# Enable_Circuit.net
KiCad netlist of a schematic drawn in EAGLE
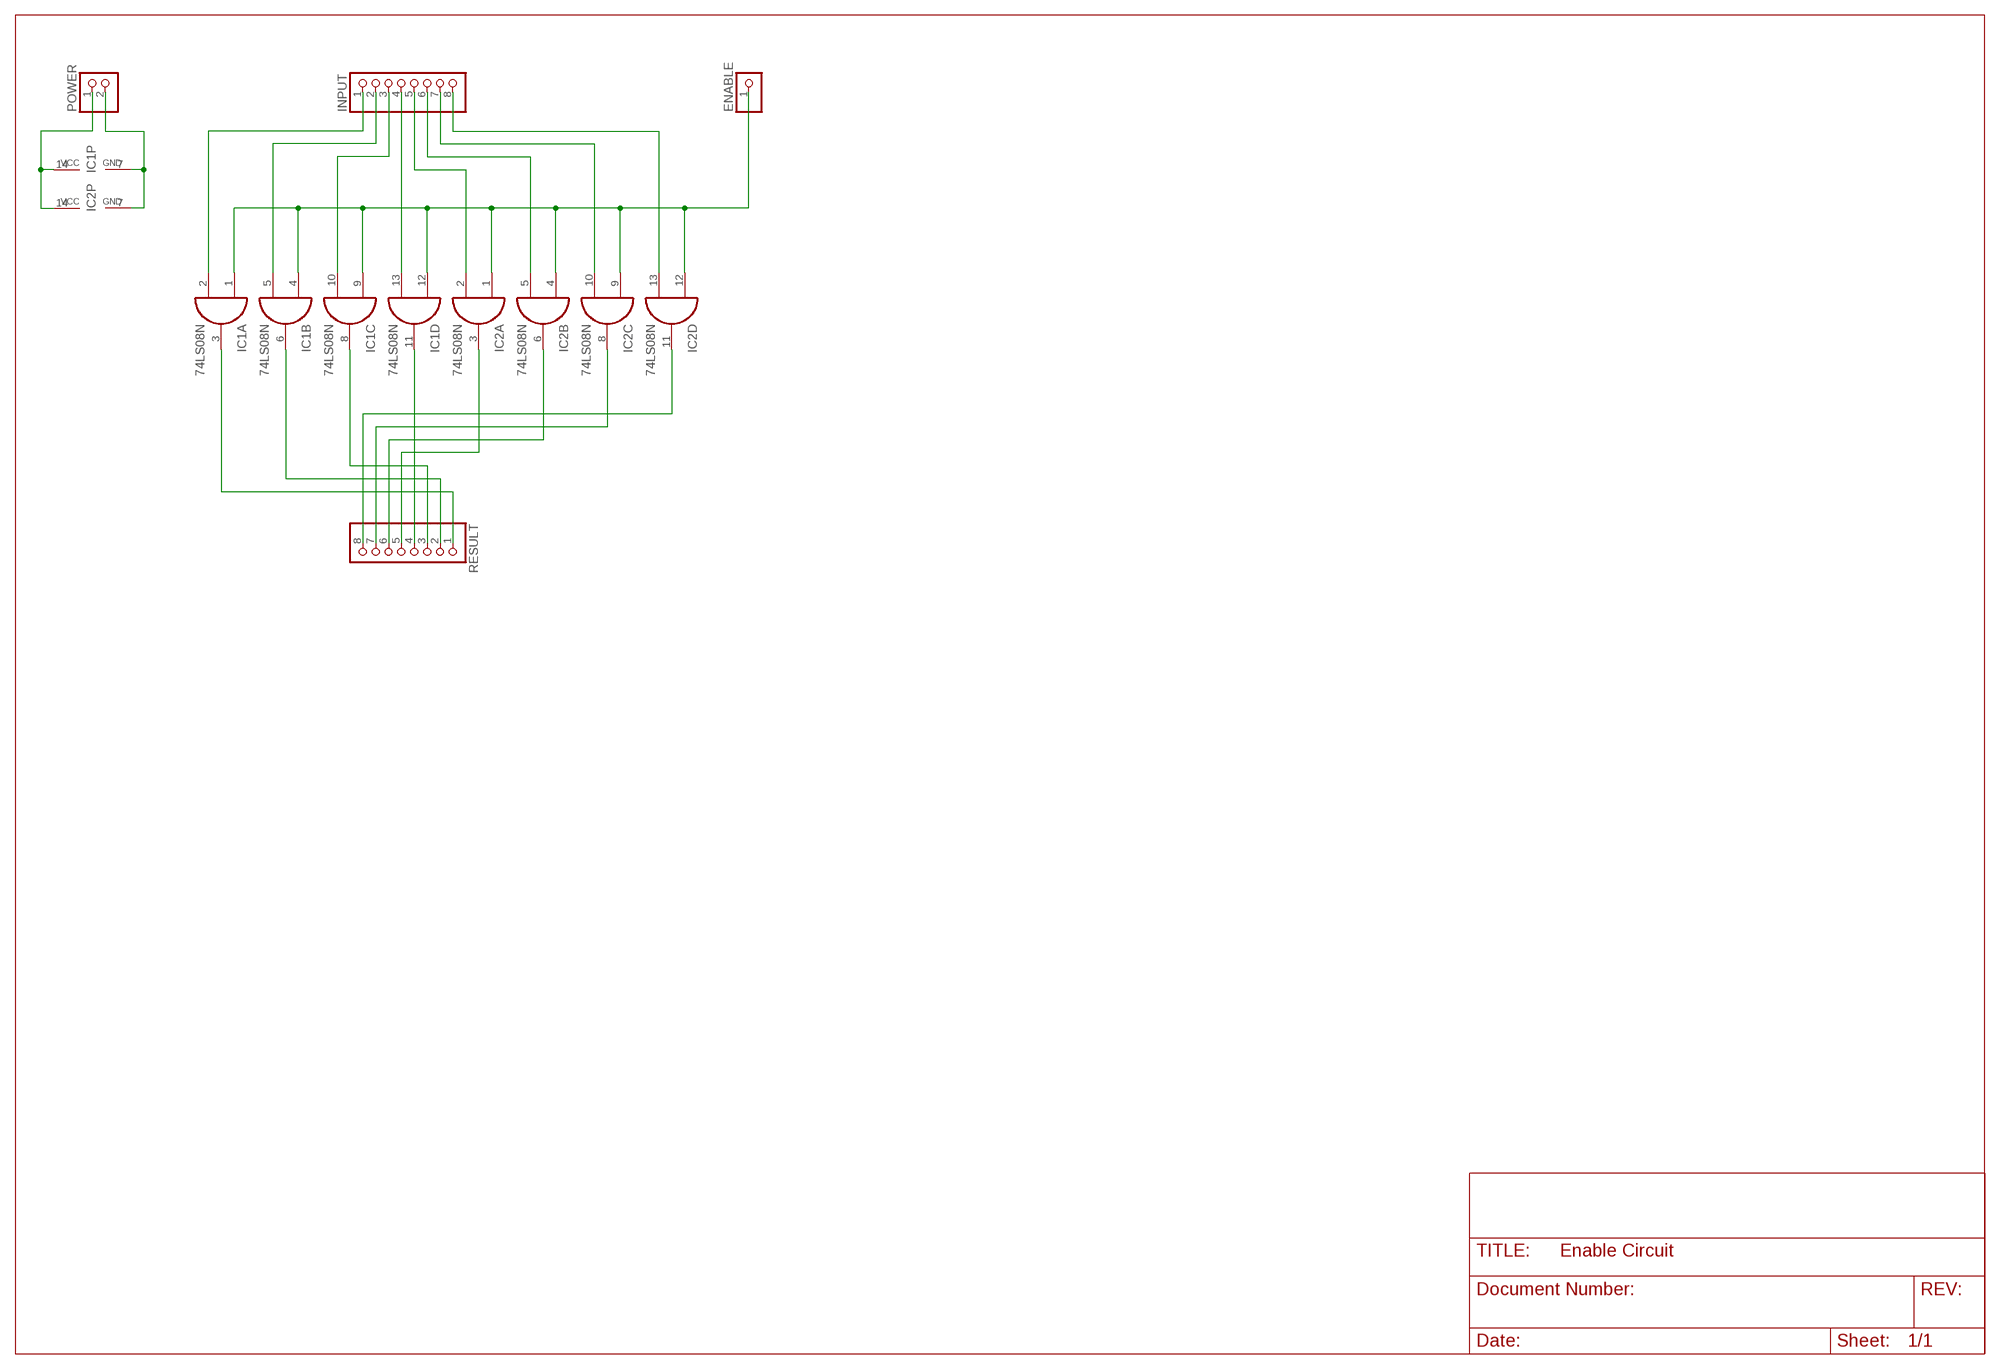
[diagram p0: schematic, sheet 1]

(export (version "E")
  (design (tool "Eeschema 10.0.6"))
  (components
    (comp (ref "ENABLE")
      (value "PINHD-1X1")
      (footprint "eagle-import:1X01")
      (libsource (lib "eagle-import") (part "PINHD-1X1"))
    )
    (comp (ref "IC1")
      (value "74LS08N")
      (footprint "eagle-import:DIL14")
      (libsource (lib "eagle-import") (part "7408NLS"))
    )
    (comp (ref "IC2")
      (value "74LS08N")
      (footprint "eagle-import:DIL14")
      (libsource (lib "eagle-import") (part "7408NLS"))
    )
    (comp (ref "INPUT")
      (value "PINHD-1X8")
      (footprint "eagle-import:1X08")
      (libsource (lib "eagle-import") (part "PINHD-1X8"))
    )
    (comp (ref "POWER")
      (value "PINHD-1X2")
      (footprint "eagle-import:1X02")
      (libsource (lib "eagle-import") (part "PINHD-1X2"))
    )
    (comp (ref "RESULT")
      (value "PINHD-1X8")
      (footprint "eagle-import:1X08")
      (libsource (lib "eagle-import") (part "PINHD-1X8"))
    )
  )
  (nets
    (net (code "1") (name "Net-(IC1A-I0)") (class "Default")
      (node (ref "ENABLE") (pin "1") (pinfunction "1_1") (pintype "passive"))
      (node (ref "IC1") (pin "1") (pinfunction "I0_1") (pintype "input"))
      (node (ref "IC1") (pin "12") (pinfunction "I0_12") (pintype "input"))
      (node (ref "IC1") (pin "4") (pinfunction "I0_4") (pintype "input"))
      (node (ref "IC1") (pin "9") (pinfunction "I0_9") (pintype "input"))
      (node (ref "IC2") (pin "1") (pinfunction "I0_1") (pintype "input"))
      (node (ref "IC2") (pin "12") (pinfunction "I0_12") (pintype "input"))
      (node (ref "IC2") (pin "4") (pinfunction "I0_4") (pintype "input"))
      (node (ref "IC2") (pin "9") (pinfunction "I0_9") (pintype "input"))
    )
    (net (code "2") (name "Net-(IC1A-I1)") (class "Default")
      (node (ref "IC1") (pin "2") (pinfunction "I1_2") (pintype "input"))
      (node (ref "INPUT") (pin "1") (pinfunction "1_1") (pintype "passive"))
    )
    (net (code "3") (name "Net-(IC1A-O)") (class "Default")
      (node (ref "IC1") (pin "3") (pinfunction "O_3") (pintype "output"))
      (node (ref "RESULT") (pin "1") (pinfunction "1_1") (pintype "passive"))
    )
    (net (code "4") (name "Net-(IC1B-I1)") (class "Default")
      (node (ref "IC1") (pin "5") (pinfunction "I1_5") (pintype "input"))
      (node (ref "INPUT") (pin "2") (pinfunction "2_2") (pintype "passive"))
    )
    (net (code "5") (name "Net-(IC1B-O)") (class "Default")
      (node (ref "IC1") (pin "6") (pinfunction "O_6") (pintype "output"))
      (node (ref "RESULT") (pin "2") (pinfunction "2_2") (pintype "passive"))
    )
    (net (code "6") (name "Net-(IC1C-I1)") (class "Default")
      (node (ref "IC1") (pin "10") (pinfunction "I1_10") (pintype "input"))
      (node (ref "INPUT") (pin "3") (pinfunction "3_3") (pintype "passive"))
    )
    (net (code "7") (name "Net-(IC1C-O)") (class "Default")
      (node (ref "IC1") (pin "8") (pinfunction "O_8") (pintype "output"))
      (node (ref "RESULT") (pin "3") (pinfunction "3_3") (pintype "passive"))
    )
    (net (code "8") (name "Net-(IC1D-I1)") (class "Default")
      (node (ref "IC1") (pin "13") (pinfunction "I1_13") (pintype "input"))
      (node (ref "INPUT") (pin "4") (pinfunction "4_4") (pintype "passive"))
    )
    (net (code "9") (name "Net-(IC1D-O)") (class "Default")
      (node (ref "IC1") (pin "11") (pinfunction "O_11") (pintype "output"))
      (node (ref "RESULT") (pin "4") (pinfunction "4_4") (pintype "passive"))
    )
    (net (code "10") (name "Net-(IC1E-GND)") (class "Default")
      (node (ref "IC1") (pin "7") (pinfunction "GND_7") (pintype "power_in"))
      (node (ref "IC2") (pin "7") (pinfunction "GND_7") (pintype "power_in"))
      (node (ref "POWER") (pin "2") (pinfunction "2_2") (pintype "passive"))
    )
    (net (code "11") (name "Net-(IC1E-VCC)") (class "Default")
      (node (ref "IC1") (pin "14") (pinfunction "VCC_14") (pintype "power_in"))
      (node (ref "IC2") (pin "14") (pinfunction "VCC_14") (pintype "power_in"))
      (node (ref "POWER") (pin "1") (pinfunction "1_1") (pintype "passive"))
    )
    (net (code "12") (name "Net-(IC2A-I1)") (class "Default")
      (node (ref "IC2") (pin "2") (pinfunction "I1_2") (pintype "input"))
      (node (ref "INPUT") (pin "5") (pinfunction "5_5") (pintype "passive"))
    )
    (net (code "13") (name "Net-(IC2A-O)") (class "Default")
      (node (ref "IC2") (pin "3") (pinfunction "O_3") (pintype "output"))
      (node (ref "RESULT") (pin "5") (pinfunction "5_5") (pintype "passive"))
    )
    (net (code "14") (name "Net-(IC2B-I1)") (class "Default")
      (node (ref "IC2") (pin "5") (pinfunction "I1_5") (pintype "input"))
      (node (ref "INPUT") (pin "6") (pinfunction "6_6") (pintype "passive"))
    )
    (net (code "15") (name "Net-(IC2B-O)") (class "Default")
      (node (ref "IC2") (pin "6") (pinfunction "O_6") (pintype "output"))
      (node (ref "RESULT") (pin "6") (pinfunction "6_6") (pintype "passive"))
    )
    (net (code "16") (name "Net-(IC2C-I1)") (class "Default")
      (node (ref "IC2") (pin "10") (pinfunction "I1_10") (pintype "input"))
      (node (ref "INPUT") (pin "7") (pinfunction "7_7") (pintype "passive"))
    )
    (net (code "17") (name "Net-(IC2C-O)") (class "Default")
      (node (ref "IC2") (pin "8") (pinfunction "O_8") (pintype "output"))
      (node (ref "RESULT") (pin "7") (pinfunction "7_7") (pintype "passive"))
    )
    (net (code "18") (name "Net-(IC2D-I1)") (class "Default")
      (node (ref "IC2") (pin "13") (pinfunction "I1_13") (pintype "input"))
      (node (ref "INPUT") (pin "8") (pinfunction "8_8") (pintype "passive"))
    )
    (net (code "19") (name "Net-(IC2D-O)") (class "Default")
      (node (ref "IC2") (pin "11") (pinfunction "O_11") (pintype "output"))
      (node (ref "RESULT") (pin "8") (pinfunction "8_8") (pintype "passive"))
    )
  )
)
